# Adafruit_Pixel_Trinkey.net
KiCad netlist of a schematic drawn in EAGLE
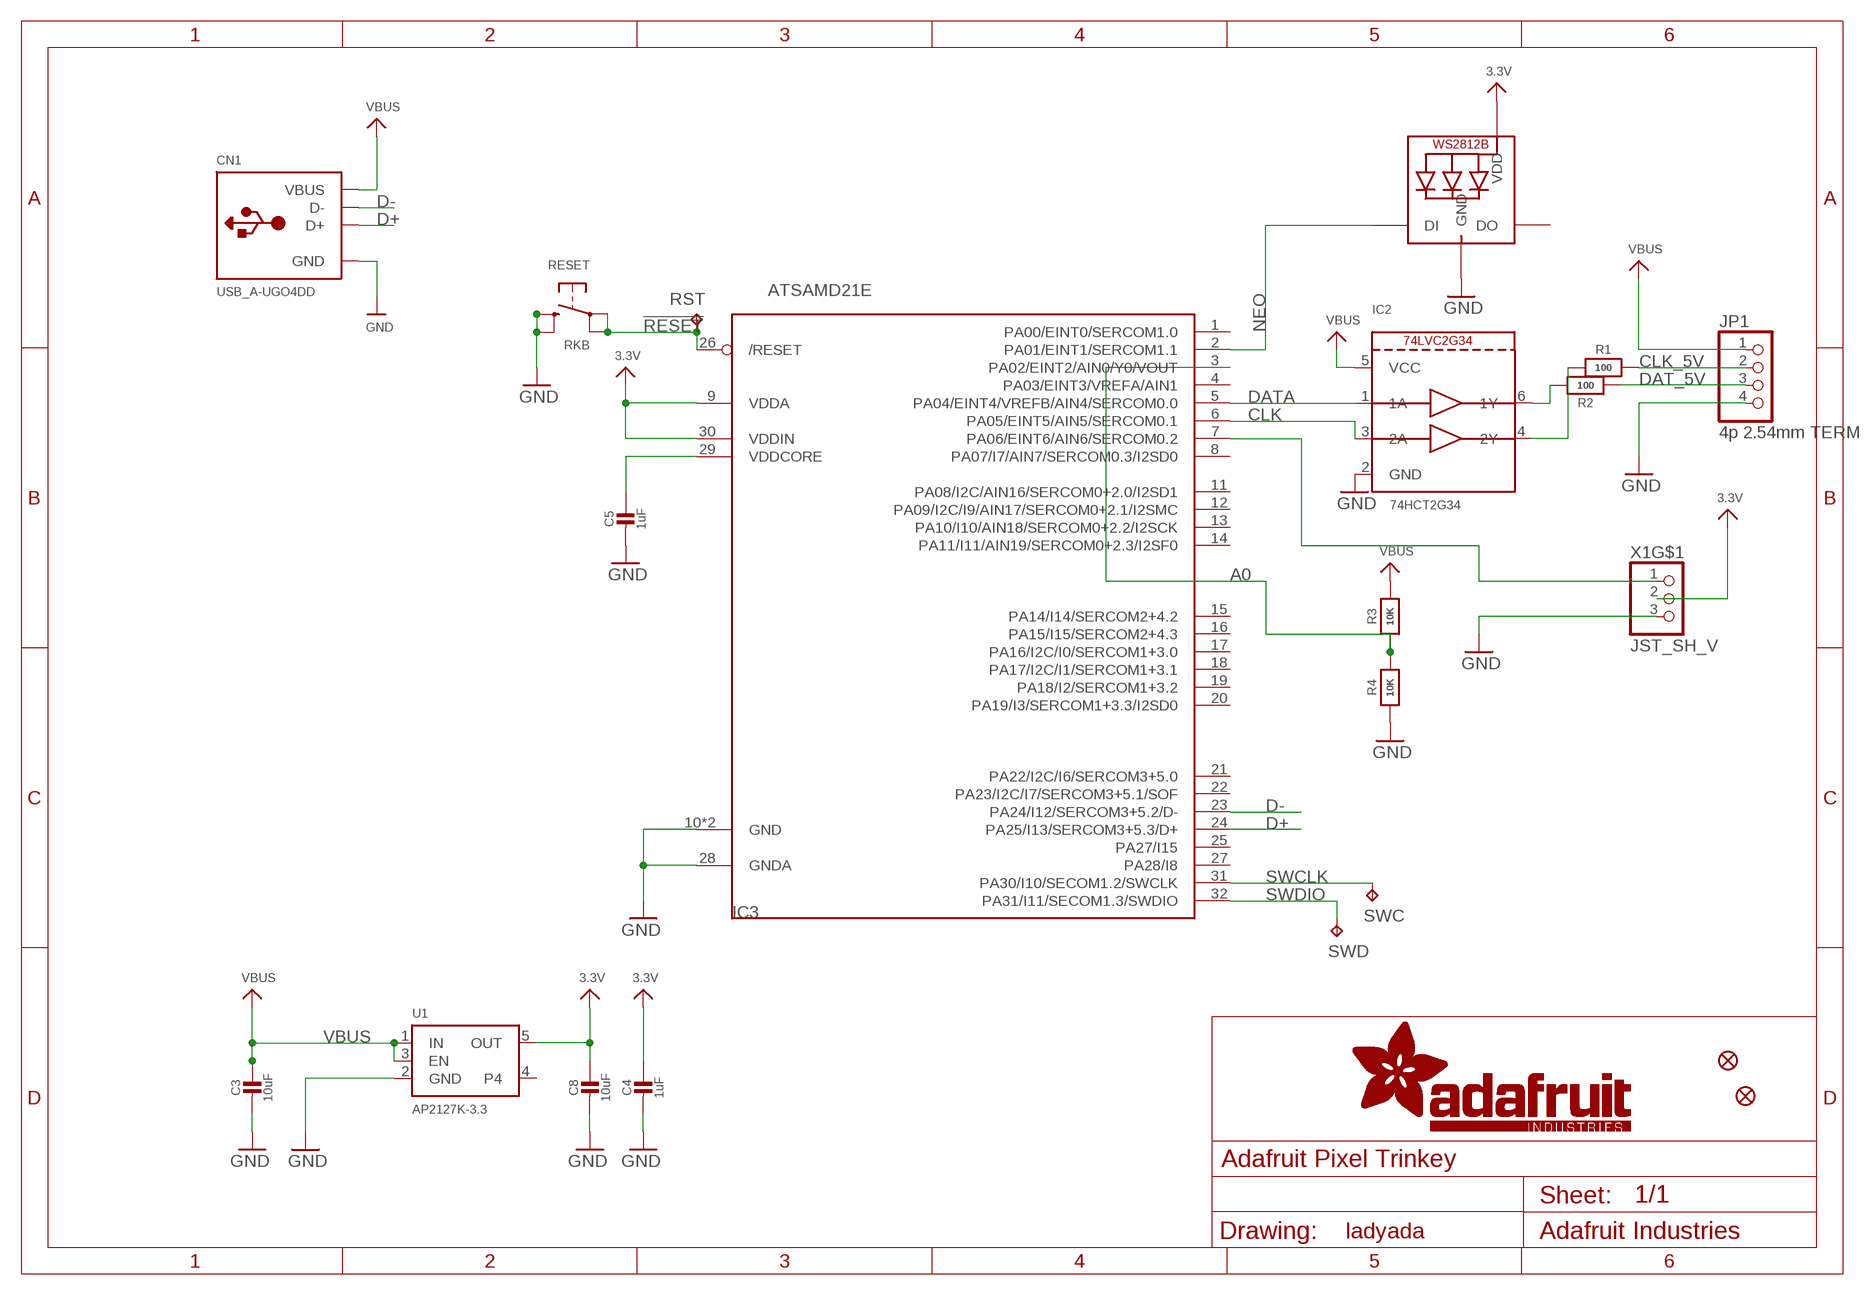
[diagram p0: schematic, sheet 1]

(export (version "E")
  (design (tool "Eeschema 10.0.6"))
  (components
    (comp (ref "C3")
      (value "10uF")
      (footprint "eagle-import:0805-NO")
      (libsource (lib "eagle-import") (part "CAP_CERAMIC0805-NOOUTLINE"))
    )
    (comp (ref "C4")
      (value "1uF")
      (footprint "eagle-import:0603-NO")
      (libsource (lib "eagle-import") (part "CAP_CERAMIC0603_NO"))
    )
    (comp (ref "C5")
      (value "1uF")
      (footprint "eagle-import:0603-NO")
      (libsource (lib "eagle-import") (part "CAP_CERAMIC0603_NO"))
    )
    (comp (ref "C8")
      (value "10uF")
      (footprint "eagle-import:0805-NO")
      (libsource (lib "eagle-import") (part "CAP_CERAMIC0805-NOOUTLINE"))
    )
    (comp (ref "CN1")
      (value "USB_A-UGO4DD")
      (footprint "eagle-import:USB_A-UGO4DD")
      (libsource (lib "eagle-import") (part "USB_TYPEA_UG04DD"))
    )
    (comp (ref "FID1")
      (value "FIDUCIAL_0.5MM")
      (footprint "eagle-import:FIDUCIAL_0.5MM")
      (libsource (lib "eagle-import") (part "FIDUCIAL_0.5MM"))
    )
    (comp (ref "FID2")
      (value "FIDUCIAL_0.5MM")
      (footprint "eagle-import:FIDUCIAL_0.5MM")
      (libsource (lib "eagle-import") (part "FIDUCIAL_0.5MM"))
    )
    (comp (ref "IC2")
      (value "74HCT2G34")
      (footprint "eagle-import:SC70-6L")
      (libsource (lib "eagle-import") (part "74LVC2G34"))
    )
    (comp (ref "IC3")
      (value "ATSAMD21E")
      (footprint "eagle-import:QFN32_5MM")
      (libsource (lib "eagle-import") (part "ATSAMD21E"))
    )
    (comp (ref "JP1")
      (value "4p 2.54mm TERM")
      (footprint "eagle-import:1X04_2.54MMTERMINAL")
      (libsource (lib "eagle-import") (part "HEADER-1X4_254MMTERM"))
    )
    (comp (ref "LED1")
      (value "WS2812B_SK6805_1515")
      (footprint "eagle-import:SK6805_1515")
      (libsource (lib "eagle-import") (part "WS2812B_SK6805_1515"))
    )
    (comp (ref "R1")
      (value "100")
      (footprint "eagle-import:_0402NO")
      (libsource (lib "eagle-import") (part "RESISTOR_0402NO"))
    )
    (comp (ref "R2")
      (value "100")
      (footprint "eagle-import:_0402NO")
      (libsource (lib "eagle-import") (part "RESISTOR_0402NO"))
    )
    (comp (ref "R3")
      (value "10K")
      (footprint "eagle-import:_0402NO")
      (libsource (lib "eagle-import") (part "RESISTOR_0402NO"))
    )
    (comp (ref "R4")
      (value "10K")
      (footprint "eagle-import:_0402NO")
      (libsource (lib "eagle-import") (part "RESISTOR_0402NO"))
    )
    (comp (ref "RESET")
      (value "RKB")
      (footprint "eagle-import:BTN_RKB2_4.6X2.8")
      (libsource (lib "eagle-import") (part "SWITCH_TACT_SMT_RKB2"))
    )
    (comp (ref "RST")
      (value "TPTP16R")
      (footprint "eagle-import:TP16R")
      (libsource (lib "eagle-import") (part "TPTP16R"))
    )
    (comp (ref "SWC")
      (value "TPTP15R")
      (footprint "eagle-import:TP15R")
      (libsource (lib "eagle-import") (part "TPTP15R"))
    )
    (comp (ref "SWD")
      (value "TPTP16R")
      (footprint "eagle-import:TP16R")
      (libsource (lib "eagle-import") (part "TPTP16R"))
    )
    (comp (ref "U1")
      (value "AP2127K-3.3")
      (footprint "eagle-import:SOT23-5")
      (fields (field (name "JLC_ROTATION") "0"))
      (libsource (lib "eagle-import") (part "VREG_SOT23-5"))
    )
    (comp (ref "X1")
      (value "JST_SH_V")
      (footprint "eagle-import:JST_SH3_RA")
      (libsource (lib "eagle-import") (part "CON_JST_SH_3PINVERT"))
    )
  )
  (nets
    (net (code "1") (name "/A0") (class "Default")
      (node (ref "IC3") (pin "3") (pinfunction "PA02/EINT2/AIN0/Y0/VOUT_3") (pintype "bidirectional"))
      (node (ref "R3") (pin "1") (pinfunction "1_1") (pintype "passive"))
      (node (ref "R4") (pin "2") (pinfunction "2_2") (pintype "passive"))
    )
    (net (code "2") (name "/CLK") (class "Default")
      (node (ref "IC2") (pin "3") (pinfunction "2A_3") (pintype "input"))
      (node (ref "IC3") (pin "6") (pinfunction "PA05/EINT5/AIN5/SERCOM0.1_6") (pintype "bidirectional"))
    )
    (net (code "3") (name "/CLK_5V") (class "Default")
      (node (ref "JP1") (pin "2") (pinfunction "2_2") (pintype "passive"))
      (node (ref "R1") (pin "2") (pinfunction "2_2") (pintype "passive"))
    )
    (net (code "4") (name "/D+") (class "Default")
      (node (ref "CN1") (pin "D+") (pinfunction "D+_D+") (pintype "bidirectional"))
      (node (ref "IC3") (pin "24") (pinfunction "PA25/I13/SERCOM3+5.3/D+_24") (pintype "bidirectional"))
    )
    (net (code "5") (name "/D-") (class "Default")
      (node (ref "CN1") (pin "D-") (pinfunction "D-_D-") (pintype "bidirectional"))
      (node (ref "IC3") (pin "23") (pinfunction "PA24/I12/SERCOM3+5.2/D-_23") (pintype "bidirectional"))
    )
    (net (code "6") (name "/DATA") (class "Default")
      (node (ref "IC2") (pin "1") (pinfunction "1A_1") (pintype "input"))
      (node (ref "IC3") (pin "5") (pinfunction "PA04/EINT4/VREFB/AIN4/SERCOM0.0_5") (pintype "bidirectional"))
    )
    (net (code "7") (name "/DAT_5V") (class "Default")
      (node (ref "JP1") (pin "3") (pinfunction "3_3") (pintype "passive"))
      (node (ref "R2") (pin "2") (pinfunction "2_2") (pintype "passive"))
    )
    (net (code "8") (name "/NEO") (class "Default")
      (node (ref "IC3") (pin "2") (pinfunction "PA01/EINT1/SERCOM1.1_2") (pintype "bidirectional"))
      (node (ref "LED1") (pin "1") (pinfunction "DI_1") (pintype "input"))
    )
    (net (code "9") (name "/SWCLK") (class "Default")
      (node (ref "IC3") (pin "31") (pinfunction "PA30/I10/SECOM1.2/SWCLK_31") (pintype "bidirectional"))
      (node (ref "SWC") (pin "TP") (pinfunction "TP_TP") (pintype "input"))
    )
    (net (code "10") (name "/SWDIO") (class "Default")
      (node (ref "IC3") (pin "32") (pinfunction "PA31/I11/SECOM1.3/SWDIO_32") (pintype "bidirectional"))
      (node (ref "SWD") (pin "TP") (pinfunction "TP_TP") (pintype "input"))
    )
    (net (code "11") (name "/~{RESET}") (class "Default")
      (node (ref "IC3") (pin "26") (pinfunction "/RESET_26") (pintype "bidirectional"))
      (node (ref "RESET") (pin "A") (pinfunction "P_A") (pintype "passive"))
      (node (ref "RESET") (pin "A'") (pinfunction "P1_A'") (pintype "passive"))
      (node (ref "RST") (pin "TP") (pinfunction "TP_TP") (pintype "input"))
    )
    (net (code "12") (name "3.3V") (class "Default")
      (node (ref "C4") (pin "1") (pinfunction "1_1") (pintype "passive"))
      (node (ref "C8") (pin "1") (pinfunction "1_1") (pintype "passive"))
      (node (ref "IC3") (pin "30") (pinfunction "VDDIN_30") (pintype "power_in"))
      (node (ref "IC3") (pin "9") (pinfunction "VDDA_9") (pintype "power_in"))
      (node (ref "LED1") (pin "2") (pinfunction "VDD_2") (pintype "power_in"))
      (node (ref "U1") (pin "5") (pinfunction "OUT_5") (pintype "power_in"))
      (node (ref "X1") (pin "2") (pinfunction "2_2") (pintype "passive"))
    )
    (net (code "13") (name "GND") (class "Default")
      (node (ref "C3") (pin "2") (pinfunction "2_2") (pintype "passive"))
      (node (ref "C4") (pin "2") (pinfunction "2_2") (pintype "passive"))
      (node (ref "C5") (pin "2") (pinfunction "2_2") (pintype "passive"))
      (node (ref "C8") (pin "2") (pinfunction "2_2") (pintype "passive"))
      (node (ref "CN1") (pin "GND") (pinfunction "GND_GND") (pintype "power_in"))
      (node (ref "IC2") (pin "2") (pinfunction "GND_2") (pintype "power_in"))
      (node (ref "IC3") (pin "10") (pinfunction "GND_10") (pintype "power_in"))
      (node (ref "IC3") (pin "28") (pinfunction "GNDA_28") (pintype "power_in"))
      (node (ref "IC3") (pin "33") (pinfunction "GND_33") (pintype "power_in"))
      (node (ref "JP1") (pin "4") (pinfunction "4_4") (pintype "passive"))
      (node (ref "LED1") (pin "4") (pinfunction "GND_4") (pintype "power_in"))
      (node (ref "R4") (pin "1") (pinfunction "1_1") (pintype "passive"))
      (node (ref "RESET") (pin "B") (pinfunction "S_B") (pintype "passive"))
      (node (ref "RESET") (pin "B'") (pinfunction "S1_B'") (pintype "passive"))
      (node (ref "U1") (pin "2") (pinfunction "GND_2") (pintype "power_in"))
      (node (ref "X1") (pin "3") (pinfunction "3_3") (pintype "passive"))
    )
    (net (code "14") (name "Net-(IC2-1Y)") (class "Default")
      (node (ref "IC2") (pin "6") (pinfunction "1Y_6") (pintype "output"))
      (node (ref "R2") (pin "1") (pinfunction "1_1") (pintype "passive"))
    )
    (net (code "15") (name "Net-(IC2-2Y)") (class "Default")
      (node (ref "IC2") (pin "4") (pinfunction "2Y_4") (pintype "output"))
      (node (ref "R1") (pin "1") (pinfunction "1_1") (pintype "passive"))
    )
    (net (code "16") (name "Net-(IC3-PA06{slash}EINT6{slash}AIN6{slash}SERCOM0.2)") (class "Default")
      (node (ref "IC3") (pin "7") (pinfunction "PA06/EINT6/AIN6/SERCOM0.2_7") (pintype "bidirectional"))
      (node (ref "X1") (pin "1") (pinfunction "1_1") (pintype "passive"))
    )
    (net (code "17") (name "Net-(IC3-VDDCORE)") (class "Default")
      (node (ref "C5") (pin "1") (pinfunction "1_1") (pintype "passive"))
      (node (ref "IC3") (pin "29") (pinfunction "VDDCORE_29") (pintype "power_in"))
    )
    (net (code "18") (name "VBUS") (class "Default")
      (node (ref "C3") (pin "1") (pinfunction "1_1") (pintype "passive"))
      (node (ref "CN1") (pin "VBUS") (pinfunction "VBUS_VBUS") (pintype "power_in"))
      (node (ref "IC2") (pin "5") (pinfunction "VCC_5") (pintype "power_in"))
      (node (ref "JP1") (pin "1") (pinfunction "1_1") (pintype "passive"))
      (node (ref "R3") (pin "2") (pinfunction "2_2") (pintype "passive"))
      (node (ref "U1") (pin "1") (pinfunction "IN_1") (pintype "power_in"))
      (node (ref "U1") (pin "3") (pinfunction "EN_3") (pintype "input"))
    )
    (net (code "19") (name "unconnected-(IC3-PA00{slash}EINT0{slash}SERCOM1.0-Pad1)") (class "Default")
      (node (ref "IC3") (pin "1") (pinfunction "PA00/EINT0/SERCOM1.0_1") (pintype "bidirectional"))
    )
    (net (code "20") (name "unconnected-(IC3-PA03{slash}EINT3{slash}VREFA{slash}AIN1-Pad4)") (class "Default")
      (node (ref "IC3") (pin "4") (pinfunction "PA03/EINT3/VREFA/AIN1_4") (pintype "bidirectional"))
    )
    (net (code "21") (name "unconnected-(IC3-PA07{slash}I7{slash}AIN7{slash}SERCOM0.3{slash}I2SD0-Pad8)") (class "Default")
      (node (ref "IC3") (pin "8") (pinfunction "PA07/I7/AIN7/SERCOM0.3/I2SD0_8") (pintype "bidirectional"))
    )
    (net (code "22") (name "unconnected-(IC3-PA08{slash}I2C{slash}AIN16{slash}SERCOM0+2.0{slash}I2SD1-Pad11)") (class "Default")
      (node (ref "IC3") (pin "11") (pinfunction "PA08/I2C/AIN16/SERCOM0+2.0/I2SD1_11") (pintype "bidirectional"))
    )
    (net (code "23") (name "unconnected-(IC3-PA09{slash}I2C{slash}I9{slash}AIN17{slash}SERCOM0+2.1{slash}I2SMC-Pad12)") (class "Default")
      (node (ref "IC3") (pin "12") (pinfunction "PA09/I2C/I9/AIN17/SERCOM0+2.1/I2SMC_12") (pintype "bidirectional"))
    )
    (net (code "24") (name "unconnected-(IC3-PA10{slash}I10{slash}AIN18{slash}SERCOM0+2.2{slash}I2SCK-Pad13)") (class "Default")
      (node (ref "IC3") (pin "13") (pinfunction "PA10/I10/AIN18/SERCOM0+2.2/I2SCK_13") (pintype "bidirectional"))
    )
    (net (code "25") (name "unconnected-(IC3-PA11{slash}I11{slash}AIN19{slash}SERCOM0+2.3{slash}I2SF0-Pad14)") (class "Default")
      (node (ref "IC3") (pin "14") (pinfunction "PA11/I11/AIN19/SERCOM0+2.3/I2SF0_14") (pintype "bidirectional"))
    )
    (net (code "26") (name "unconnected-(IC3-PA14{slash}I14{slash}SERCOM2+4.2-Pad15)") (class "Default")
      (node (ref "IC3") (pin "15") (pinfunction "PA14/I14/SERCOM2+4.2_15") (pintype "bidirectional"))
    )
    (net (code "27") (name "unconnected-(IC3-PA15{slash}I15{slash}SERCOM2+4.3-Pad16)") (class "Default")
      (node (ref "IC3") (pin "16") (pinfunction "PA15/I15/SERCOM2+4.3_16") (pintype "bidirectional"))
    )
    (net (code "28") (name "unconnected-(IC3-PA16{slash}I2C{slash}I0{slash}SERCOM1+3.0-Pad17)") (class "Default")
      (node (ref "IC3") (pin "17") (pinfunction "PA16/I2C/I0/SERCOM1+3.0_17") (pintype "bidirectional"))
    )
    (net (code "29") (name "unconnected-(IC3-PA17{slash}I2C{slash}I1{slash}SERCOM1+3.1-Pad18)") (class "Default")
      (node (ref "IC3") (pin "18") (pinfunction "PA17/I2C/I1/SERCOM1+3.1_18") (pintype "bidirectional"))
    )
    (net (code "30") (name "unconnected-(IC3-PA18{slash}I2{slash}SERCOM1+3.2-Pad19)") (class "Default")
      (node (ref "IC3") (pin "19") (pinfunction "PA18/I2/SERCOM1+3.2_19") (pintype "bidirectional"))
    )
    (net (code "31") (name "unconnected-(IC3-PA19{slash}I3{slash}SERCOM1+3.3{slash}I2SD0-Pad20)") (class "Default")
      (node (ref "IC3") (pin "20") (pinfunction "PA19/I3/SERCOM1+3.3/I2SD0_20") (pintype "bidirectional"))
    )
    (net (code "32") (name "unconnected-(IC3-PA22{slash}I2C{slash}I6{slash}SERCOM3+5.0-Pad21)") (class "Default")
      (node (ref "IC3") (pin "21") (pinfunction "PA22/I2C/I6/SERCOM3+5.0_21") (pintype "bidirectional"))
    )
    (net (code "33") (name "unconnected-(IC3-PA23{slash}I2C{slash}I7{slash}SERCOM3+5.1{slash}SOF-Pad22)") (class "Default")
      (node (ref "IC3") (pin "22") (pinfunction "PA23/I2C/I7/SERCOM3+5.1/SOF_22") (pintype "bidirectional"))
    )
    (net (code "34") (name "unconnected-(IC3-PA27{slash}I15-Pad25)") (class "Default")
      (node (ref "IC3") (pin "25") (pinfunction "PA27/I15_25") (pintype "bidirectional"))
    )
    (net (code "35") (name "unconnected-(IC3-PA28{slash}I8-Pad27)") (class "Default")
      (node (ref "IC3") (pin "27") (pinfunction "PA28/I8_27") (pintype "bidirectional"))
    )
    (net (code "36") (name "unconnected-(LED1-DO-Pad3)") (class "Default")
      (node (ref "LED1") (pin "3") (pinfunction "DO_3") (pintype "output"))
    )
    (net (code "37") (name "unconnected-(U1-P4-Pad4)") (class "Default")
      (node (ref "U1") (pin "4") (pinfunction "P4_4") (pintype "bidirectional"))
    )
  )
)
